# tiva_motor.net
KiCad netlist of a schematic drawn in EAGLE
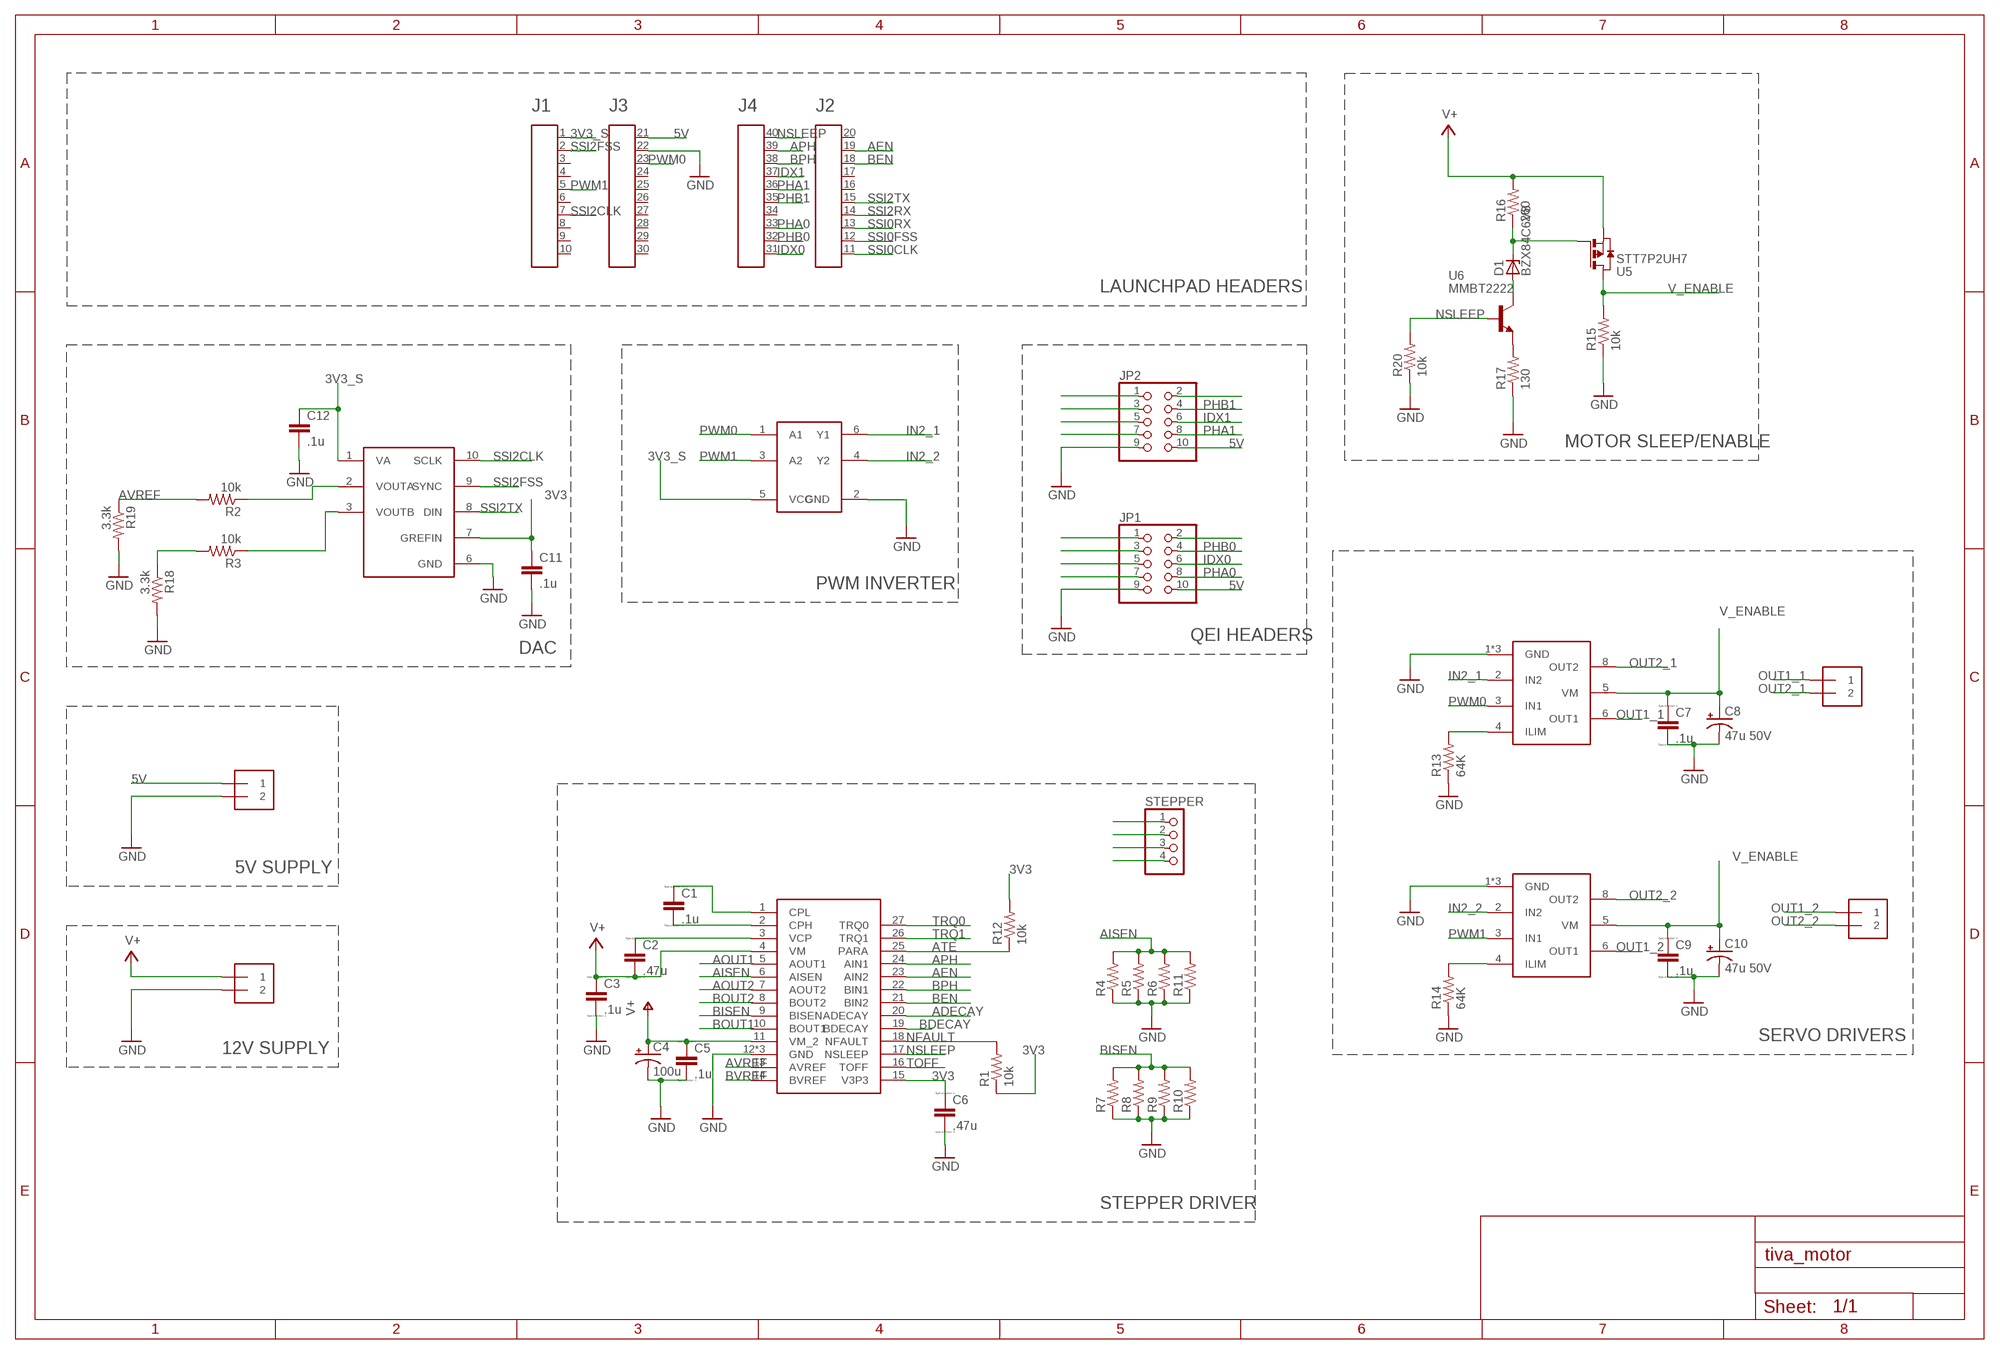
[diagram p0: schematic, sheet 1]

(export (version "E")
  (design (tool "Eeschema 10.0.6"))
  (components
    (comp (ref "5V")
      (value "1X2-3.5MM")
      (footprint "eagle-import:1X2-3.5MM")
      (libsource (lib "eagle-import") (part "1X2-3.5MM"))
    )
    (comp (ref "12V")
      (value "1X2-3.5MM")
      (footprint "eagle-import:1X2-3.5MM")
      (libsource (lib "eagle-import") (part "1X2-3.5MM"))
    )
    (comp (ref "A1")
      (value "HEADER4X10-BOOSTERPACK")
      (footprint "eagle-import:4X10-BOOSTERPACK")
      (libsource (lib "eagle-import") (part "HEADER4X10-BOOSTERPACK"))
    )
    (comp (ref "C1")
      (value ".1u")
      (footprint "eagle-import:C0603")
      (libsource (lib "eagle-import") (part "CC0603"))
    )
    (comp (ref "C2")
      (value ".47u")
      (footprint "eagle-import:C0603")
      (libsource (lib "eagle-import") (part "CC0603"))
    )
    (comp (ref "C3")
      (value ".1u")
      (footprint "eagle-import:C0603")
      (libsource (lib "eagle-import") (part "CC0603"))
    )
    (comp (ref "C4")
      (value "100u")
      (footprint "eagle-import:153CLV-0605")
      (libsource (lib "eagle-import") (part "CPOL-US153CLV-0605"))
    )
    (comp (ref "C5")
      (value ".1u")
      (footprint "eagle-import:C0603")
      (libsource (lib "eagle-import") (part "CC0603"))
    )
    (comp (ref "C6")
      (value ".47u")
      (footprint "eagle-import:C0603")
      (libsource (lib "eagle-import") (part "CC0603"))
    )
    (comp (ref "C7")
      (value ".1u")
      (footprint "eagle-import:C0603")
      (libsource (lib "eagle-import") (part "CC0603"))
    )
    (comp (ref "C8")
      (value "47u 50V")
      (footprint "eagle-import:153CLV-0605")
      (libsource (lib "eagle-import") (part "CPOL-US153CLV-0605"))
    )
    (comp (ref "C9")
      (value ".1u")
      (footprint "eagle-import:C0603")
      (libsource (lib "eagle-import") (part "CC0603"))
    )
    (comp (ref "C10")
      (value "47u 50V")
      (footprint "eagle-import:153CLV-0605")
      (libsource (lib "eagle-import") (part "CPOL-US153CLV-0605"))
    )
    (comp (ref "C11")
      (value ".1u")
      (footprint "eagle-import:C0402")
      (libsource (lib "eagle-import") (part "C-EUC0402"))
    )
    (comp (ref "C12")
      (value ".1u")
      (footprint "eagle-import:C0402")
      (libsource (lib "eagle-import") (part "C-EUC0402"))
    )
    (comp (ref "D1")
      (value "BZX84C6V8")
      (footprint "eagle-import:SOT-23")
      (libsource (lib "eagle-import") (part "BZX84C6V8"))
    )
    (comp (ref "JP1")
      (value "PINHD-2X5")
      (footprint "eagle-import:2X05")
      (libsource (lib "eagle-import") (part "PINHD-2X5"))
    )
    (comp (ref "JP2")
      (value "PINHD-2X5")
      (footprint "eagle-import:2X05")
      (libsource (lib "eagle-import") (part "PINHD-2X5"))
    )
    (comp (ref "M1")
      (value "1X2-3.5MM")
      (footprint "eagle-import:1X2-3.5MM")
      (libsource (lib "eagle-import") (part "1X2-3.5MM"))
    )
    (comp (ref "M2")
      (value "1X2-3.5MM")
      (footprint "eagle-import:1X2-3.5MM")
      (libsource (lib "eagle-import") (part "1X2-3.5MM"))
    )
    (comp (ref "R1")
      (value "10k")
      (footprint "eagle-import:R0402")
      (libsource (lib "eagle-import") (part "R-US_R0402"))
    )
    (comp (ref "R2")
      (value "10k")
      (footprint "eagle-import:R0603")
      (libsource (lib "eagle-import") (part "R-US_R0603"))
    )
    (comp (ref "R3")
      (value "10k")
      (footprint "eagle-import:R0603")
      (libsource (lib "eagle-import") (part "R-US_R0603"))
    )
    (comp (ref "R4")
      (value "R-US_R0603")
      (footprint "eagle-import:R0603")
      (libsource (lib "eagle-import") (part "R-US_R0603"))
    )
    (comp (ref "R5")
      (value "R-US_R0603")
      (footprint "eagle-import:R0603")
      (libsource (lib "eagle-import") (part "R-US_R0603"))
    )
    (comp (ref "R6")
      (value "R-US_R0603")
      (footprint "eagle-import:R0603")
      (libsource (lib "eagle-import") (part "R-US_R0603"))
    )
    (comp (ref "R7")
      (value "R-US_R0603")
      (footprint "eagle-import:R0603")
      (libsource (lib "eagle-import") (part "R-US_R0603"))
    )
    (comp (ref "R8")
      (value "R-US_R0603")
      (footprint "eagle-import:R0603")
      (libsource (lib "eagle-import") (part "R-US_R0603"))
    )
    (comp (ref "R9")
      (value "R-US_R0603")
      (footprint "eagle-import:R0603")
      (libsource (lib "eagle-import") (part "R-US_R0603"))
    )
    (comp (ref "R10")
      (value "R-US_R0603")
      (footprint "eagle-import:R0603")
      (libsource (lib "eagle-import") (part "R-US_R0603"))
    )
    (comp (ref "R11")
      (value "R-US_R0603")
      (footprint "eagle-import:R0603")
      (libsource (lib "eagle-import") (part "R-US_R0603"))
    )
    (comp (ref "R12")
      (value "10k")
      (footprint "eagle-import:R0402")
      (libsource (lib "eagle-import") (part "R-US_R0402"))
    )
    (comp (ref "R13")
      (value "64K")
      (footprint "eagle-import:R0603")
      (libsource (lib "eagle-import") (part "R-US_R0603"))
    )
    (comp (ref "R14")
      (value "64K")
      (footprint "eagle-import:R0603")
      (libsource (lib "eagle-import") (part "R-US_R0603"))
    )
    (comp (ref "R15")
      (value "10k")
      (footprint "eagle-import:R0402")
      (libsource (lib "eagle-import") (part "R-US_R0402"))
    )
    (comp (ref "R16")
      (value "260")
      (footprint "eagle-import:R0805")
      (libsource (lib "eagle-import") (part "R-US_R0805"))
    )
    (comp (ref "R17")
      (value "130")
      (footprint "eagle-import:R1206")
      (libsource (lib "eagle-import") (part "R-US_R1206"))
    )
    (comp (ref "R18")
      (value "3.3k")
      (footprint "eagle-import:R0603")
      (libsource (lib "eagle-import") (part "R-US_R0603"))
    )
    (comp (ref "R19")
      (value "3.3k")
      (footprint "eagle-import:R0603")
      (libsource (lib "eagle-import") (part "R-US_R0603"))
    )
    (comp (ref "R20")
      (value "10k")
      (footprint "eagle-import:R0402")
      (libsource (lib "eagle-import") (part "R-US_R0402"))
    )
    (comp (ref "STEPPER")
      (value "PINHD-1X4")
      (footprint "eagle-import:1X04")
      (libsource (lib "eagle-import") (part "PINHD-1X4"))
    )
    (comp (ref "U1")
      (value "DRV8881")
      (footprint "eagle-import:TSSOP28")
      (libsource (lib "eagle-import") (part "DRV8881"))
    )
    (comp (ref "U2")
      (value "DRV8871")
      (footprint "eagle-import:SOIC127P600X170-9N")
      (libsource (lib "eagle-import") (part "DRV8871"))
    )
    (comp (ref "U4")
      (value "DRV8871")
      (footprint "eagle-import:SOIC127P600X170-9N")
      (libsource (lib "eagle-import") (part "DRV8871"))
    )
    (comp (ref "U5")
      (value "STT7P2UH7")
      (footprint "eagle-import:SOT23-6")
      (libsource (lib "eagle-import") (part "STT7P2UH7"))
    )
    (comp (ref "U6")
      (value "MMBT2222")
      (footprint "eagle-import:SOT-23")
      (libsource (lib "eagle-import") (part "MMBT2222"))
    )
    (comp (ref "U8")
      (value "DAC082S085")
      (footprint "eagle-import:SOP50P490X110-10N")
      (libsource (lib "eagle-import") (part "DAC082S085"))
    )
    (comp (ref "U9")
      (value "NC7WZ14")
      (footprint "eagle-import:SC70-6")
      (libsource (lib "eagle-import") (part "NC7WZ14"))
    )
  )
  (nets
    (net (code "1") (name "/3V3") (class "Default")
      (node (ref "C11") (pin "1") (pinfunction "1_1") (pintype "passive"))
      (node (ref "C6") (pin "1") (pinfunction "1_1") (pintype "passive"))
      (node (ref "R1") (pin "1") (pinfunction "1_1") (pintype "passive"))
      (node (ref "R12") (pin "2") (pinfunction "2_2") (pintype "passive"))
      (node (ref "U1") (pin "15") (pinfunction "V3P3_15") (pintype "bidirectional"))
      (node (ref "U8") (pin "7") (pinfunction "GREFIN_7") (pintype "bidirectional"))
    )
    (net (code "2") (name "/3V3_S") (class "Default")
      (node (ref "A1") (pin "1") (pinfunction "P$1_1") (pintype "bidirectional"))
      (node (ref "C12") (pin "1") (pinfunction "1_1") (pintype "passive"))
      (node (ref "U8") (pin "1") (pinfunction "VA_1") (pintype "bidirectional"))
      (node (ref "U9") (pin "5") (pinfunction "VCC_5") (pintype "bidirectional"))
    )
    (net (code "3") (name "/5V") (class "Default")
      (node (ref "5V") (pin "1") (pinfunction "1_1") (pintype "passive"))
      (node (ref "A1") (pin "21") (pinfunction "P$21_21") (pintype "bidirectional"))
      (node (ref "JP1") (pin "10") (pinfunction "10_10") (pintype "passive"))
      (node (ref "JP2") (pin "10") (pinfunction "10_10") (pintype "passive"))
    )
    (net (code "4") (name "/ADECAY") (class "Default")
      (node (ref "U1") (pin "20") (pinfunction "ADECAY_20") (pintype "bidirectional"))
    )
    (net (code "5") (name "/AEN") (class "Default")
      (node (ref "A1") (pin "19") (pinfunction "P$19_19") (pintype "bidirectional"))
      (node (ref "U1") (pin "23") (pinfunction "AIN2_23") (pintype "bidirectional"))
    )
    (net (code "6") (name "/AISEN") (class "Default")
      (node (ref "R11") (pin "2") (pinfunction "2_2") (pintype "passive"))
      (node (ref "R4") (pin "2") (pinfunction "2_2") (pintype "passive"))
      (node (ref "R5") (pin "2") (pinfunction "2_2") (pintype "passive"))
      (node (ref "R6") (pin "2") (pinfunction "2_2") (pintype "passive"))
      (node (ref "U1") (pin "6") (pinfunction "AISEN_6") (pintype "bidirectional"))
    )
    (net (code "7") (name "/AOUT1") (class "Default")
      (node (ref "STEPPER") (pin "1") (pinfunction "1_1") (pintype "passive"))
      (node (ref "U1") (pin "5") (pinfunction "AOUT1_5") (pintype "bidirectional"))
    )
    (net (code "8") (name "/AOUT2") (class "Default")
      (node (ref "STEPPER") (pin "2") (pinfunction "2_2") (pintype "passive"))
      (node (ref "U1") (pin "7") (pinfunction "AOUT2_7") (pintype "bidirectional"))
    )
    (net (code "9") (name "/APH") (class "Default")
      (node (ref "A1") (pin "39") (pinfunction "P$39_39") (pintype "bidirectional"))
      (node (ref "U1") (pin "24") (pinfunction "AIN1_24") (pintype "bidirectional"))
    )
    (net (code "10") (name "/ATE") (class "Default")
      (node (ref "R12") (pin "1") (pinfunction "1_1") (pintype "passive"))
      (node (ref "U1") (pin "25") (pinfunction "PARA_25") (pintype "bidirectional"))
    )
    (net (code "11") (name "/AVREF") (class "Default")
      (node (ref "R19") (pin "1") (pinfunction "1_1") (pintype "passive"))
      (node (ref "R2") (pin "2") (pinfunction "2_2") (pintype "passive"))
      (node (ref "U1") (pin "13") (pinfunction "AVREF_13") (pintype "bidirectional"))
    )
    (net (code "12") (name "/BDECAY") (class "Default")
      (node (ref "U1") (pin "19") (pinfunction "BDECAY_19") (pintype "bidirectional"))
    )
    (net (code "13") (name "/BEN") (class "Default")
      (node (ref "A1") (pin "18") (pinfunction "P$18_18") (pintype "bidirectional"))
      (node (ref "U1") (pin "21") (pinfunction "BIN2_21") (pintype "bidirectional"))
    )
    (net (code "14") (name "/BISEN") (class "Default")
      (node (ref "R10") (pin "2") (pinfunction "2_2") (pintype "passive"))
      (node (ref "R7") (pin "2") (pinfunction "2_2") (pintype "passive"))
      (node (ref "R8") (pin "2") (pinfunction "2_2") (pintype "passive"))
      (node (ref "R9") (pin "2") (pinfunction "2_2") (pintype "passive"))
      (node (ref "U1") (pin "9") (pinfunction "BISEN_9") (pintype "bidirectional"))
    )
    (net (code "15") (name "/BOUT1") (class "Default")
      (node (ref "STEPPER") (pin "3") (pinfunction "3_3") (pintype "passive"))
      (node (ref "U1") (pin "10") (pinfunction "BOUT1_10") (pintype "bidirectional"))
    )
    (net (code "16") (name "/BOUT2") (class "Default")
      (node (ref "STEPPER") (pin "4") (pinfunction "4_4") (pintype "passive"))
      (node (ref "U1") (pin "8") (pinfunction "BOUT2_8") (pintype "bidirectional"))
    )
    (net (code "17") (name "/BPH") (class "Default")
      (node (ref "A1") (pin "38") (pinfunction "P$38_38") (pintype "bidirectional"))
      (node (ref "U1") (pin "22") (pinfunction "BIN1_22") (pintype "bidirectional"))
    )
    (net (code "18") (name "/BVREF") (class "Default")
      (node (ref "R18") (pin "1") (pinfunction "1_1") (pintype "passive"))
      (node (ref "R3") (pin "2") (pinfunction "2_2") (pintype "passive"))
      (node (ref "U1") (pin "14") (pinfunction "BVREF_14") (pintype "bidirectional"))
    )
    (net (code "19") (name "/IDX0") (class "Default")
      (node (ref "A1") (pin "31") (pinfunction "P$31_31") (pintype "bidirectional"))
      (node (ref "JP1") (pin "6") (pinfunction "6_6") (pintype "passive"))
    )
    (net (code "20") (name "/IDX1") (class "Default")
      (node (ref "A1") (pin "37") (pinfunction "P$37_37") (pintype "bidirectional"))
      (node (ref "JP2") (pin "6") (pinfunction "6_6") (pintype "passive"))
    )
    (net (code "21") (name "/IN2_1") (class "Default")
      (node (ref "U2") (pin "2") (pinfunction "IN2_2") (pintype "bidirectional"))
      (node (ref "U9") (pin "6") (pinfunction "Y1_6") (pintype "bidirectional"))
    )
    (net (code "22") (name "/IN2_2") (class "Default")
      (node (ref "U4") (pin "2") (pinfunction "IN2_2") (pintype "bidirectional"))
      (node (ref "U9") (pin "4") (pinfunction "Y2_4") (pintype "bidirectional"))
    )
    (net (code "23") (name "/NFAULT") (class "Default")
      (node (ref "R1") (pin "2") (pinfunction "2_2") (pintype "passive"))
      (node (ref "U1") (pin "18") (pinfunction "NFAULT_18") (pintype "bidirectional"))
    )
    (net (code "24") (name "/NSLEEP") (class "Default")
      (node (ref "A1") (pin "40") (pinfunction "P$40_40") (pintype "bidirectional"))
      (node (ref "R20") (pin "2") (pinfunction "2_2") (pintype "passive"))
      (node (ref "U1") (pin "17") (pinfunction "NSLEEP_17") (pintype "bidirectional"))
      (node (ref "U6") (pin "1") (pinfunction "B_1") (pintype "passive"))
    )
    (net (code "25") (name "/OUT1_1") (class "Default")
      (node (ref "M1") (pin "1") (pinfunction "1_1") (pintype "passive"))
      (node (ref "U2") (pin "6") (pinfunction "OUT1_6") (pintype "bidirectional"))
    )
    (net (code "26") (name "/OUT1_2") (class "Default")
      (node (ref "M2") (pin "1") (pinfunction "1_1") (pintype "passive"))
      (node (ref "U4") (pin "6") (pinfunction "OUT1_6") (pintype "bidirectional"))
    )
    (net (code "27") (name "/OUT2_1") (class "Default")
      (node (ref "M1") (pin "2") (pinfunction "2_2") (pintype "passive"))
      (node (ref "U2") (pin "8") (pinfunction "OUT2_8") (pintype "bidirectional"))
    )
    (net (code "28") (name "/OUT2_2") (class "Default")
      (node (ref "M2") (pin "2") (pinfunction "2_2") (pintype "passive"))
      (node (ref "U4") (pin "8") (pinfunction "OUT2_8") (pintype "bidirectional"))
    )
    (net (code "29") (name "/PHA0") (class "Default")
      (node (ref "A1") (pin "33") (pinfunction "P$33_33") (pintype "bidirectional"))
      (node (ref "JP1") (pin "8") (pinfunction "8_8") (pintype "passive"))
    )
    (net (code "30") (name "/PHA1") (class "Default")
      (node (ref "A1") (pin "36") (pinfunction "P$36_36") (pintype "bidirectional"))
      (node (ref "JP2") (pin "8") (pinfunction "8_8") (pintype "passive"))
    )
    (net (code "31") (name "/PHB0") (class "Default")
      (node (ref "A1") (pin "32") (pinfunction "P$32_32") (pintype "bidirectional"))
      (node (ref "JP1") (pin "4") (pinfunction "4_4") (pintype "passive"))
    )
    (net (code "32") (name "/PHB1") (class "Default")
      (node (ref "A1") (pin "35") (pinfunction "P$35_35") (pintype "bidirectional"))
      (node (ref "JP2") (pin "4") (pinfunction "4_4") (pintype "passive"))
    )
    (net (code "33") (name "/PWM0") (class "Default")
      (node (ref "A1") (pin "23") (pinfunction "P$23_23") (pintype "bidirectional"))
      (node (ref "U2") (pin "3") (pinfunction "IN1_3") (pintype "bidirectional"))
      (node (ref "U9") (pin "1") (pinfunction "A1_1") (pintype "bidirectional"))
    )
    (net (code "34") (name "/PWM1") (class "Default")
      (node (ref "A1") (pin "5") (pinfunction "P$5_5") (pintype "bidirectional"))
      (node (ref "U4") (pin "3") (pinfunction "IN1_3") (pintype "bidirectional"))
      (node (ref "U9") (pin "3") (pinfunction "A2_3") (pintype "bidirectional"))
    )
    (net (code "35") (name "/SSI0CLK") (class "Default")
      (node (ref "A1") (pin "11") (pinfunction "P$11_11") (pintype "bidirectional"))
    )
    (net (code "36") (name "/SSI0FSS") (class "Default")
      (node (ref "A1") (pin "12") (pinfunction "P$12_12") (pintype "bidirectional"))
    )
    (net (code "37") (name "/SSI0RX") (class "Default")
      (node (ref "A1") (pin "13") (pinfunction "P$13_13") (pintype "bidirectional"))
    )
    (net (code "38") (name "/SSI2CLK") (class "Default")
      (node (ref "A1") (pin "7") (pinfunction "P$7_7") (pintype "bidirectional"))
      (node (ref "U8") (pin "10") (pinfunction "SCLK_10") (pintype "bidirectional"))
    )
    (net (code "39") (name "/SSI2FSS") (class "Default")
      (node (ref "A1") (pin "2") (pinfunction "P$2_2") (pintype "bidirectional"))
      (node (ref "U8") (pin "9") (pinfunction "SYNC_9") (pintype "bidirectional"))
    )
    (net (code "40") (name "/SSI2RX") (class "Default")
      (node (ref "A1") (pin "14") (pinfunction "P$14_14") (pintype "bidirectional"))
    )
    (net (code "41") (name "/SSI2TX") (class "Default")
      (node (ref "A1") (pin "15") (pinfunction "P$15_15") (pintype "bidirectional"))
      (node (ref "U8") (pin "8") (pinfunction "DIN_8") (pintype "bidirectional"))
    )
    (net (code "42") (name "/TOFF") (class "Default")
      (node (ref "U1") (pin "16") (pinfunction "TOFF_16") (pintype "bidirectional"))
    )
    (net (code "43") (name "/TRQ0") (class "Default")
      (node (ref "U1") (pin "27") (pinfunction "TRQ0_27") (pintype "bidirectional"))
    )
    (net (code "44") (name "/TRQ1") (class "Default")
      (node (ref "U1") (pin "26") (pinfunction "TRQ1_26") (pintype "bidirectional"))
    )
    (net (code "45") (name "/V_ENABLE") (class "Default")
      (node (ref "C10") (pin "+") (pinfunction "+_+") (pintype "passive"))
      (node (ref "C7") (pin "1") (pinfunction "1_1") (pintype "passive"))
      (node (ref "C8") (pin "+") (pinfunction "+_+") (pintype "passive"))
      (node (ref "C9") (pin "1") (pinfunction "1_1") (pintype "passive"))
      (node (ref "R15") (pin "2") (pinfunction "2_2") (pintype "passive"))
      (node (ref "U2") (pin "5") (pinfunction "VM_5") (pintype "bidirectional"))
      (node (ref "U4") (pin "5") (pinfunction "VM_5") (pintype "bidirectional"))
      (node (ref "U5") (pin "1") (pinfunction "D_1") (pintype "passive"))
      (node (ref "U5") (pin "2") (pinfunction "D_2") (pintype "passive"))
      (node (ref "U5") (pin "5") (pinfunction "D_5") (pintype "passive"))
      (node (ref "U5") (pin "6") (pinfunction "D_6") (pintype "passive"))
    )
    (net (code "46") (name "GND") (class "Default")
      (node (ref "12V") (pin "2") (pinfunction "2_2") (pintype "passive"))
      (node (ref "5V") (pin "2") (pinfunction "2_2") (pintype "passive"))
      (node (ref "A1") (pin "22") (pinfunction "P$22_22") (pintype "bidirectional"))
      (node (ref "C10") (pin "-") (pinfunction "-_-") (pintype "passive"))
      (node (ref "C11") (pin "2") (pinfunction "2_2") (pintype "passive"))
      (node (ref "C12") (pin "2") (pinfunction "2_2") (pintype "passive"))
      (node (ref "C3") (pin "2") (pinfunction "2_2") (pintype "passive"))
      (node (ref "C4") (pin "-") (pinfunction "-_-") (pintype "passive"))
      (node (ref "C5") (pin "2") (pinfunction "2_2") (pintype "passive"))
      (node (ref "C6") (pin "2") (pinfunction "2_2") (pintype "passive"))
      (node (ref "C7") (pin "2") (pinfunction "2_2") (pintype "passive"))
      (node (ref "C8") (pin "-") (pinfunction "-_-") (pintype "passive"))
      (node (ref "C9") (pin "2") (pinfunction "2_2") (pintype "passive"))
      (node (ref "JP1") (pin "9") (pinfunction "9_9") (pintype "passive"))
      (node (ref "JP2") (pin "9") (pinfunction "9_9") (pintype "passive"))
      (node (ref "R10") (pin "1") (pinfunction "1_1") (pintype "passive"))
      (node (ref "R11") (pin "1") (pinfunction "1_1") (pintype "passive"))
      (node (ref "R13") (pin "1") (pinfunction "1_1") (pintype "passive"))
      (node (ref "R14") (pin "1") (pinfunction "1_1") (pintype "passive"))
      (node (ref "R15") (pin "1") (pinfunction "1_1") (pintype "passive"))
      (node (ref "R17") (pin "1") (pinfunction "1_1") (pintype "passive"))
      (node (ref "R18") (pin "2") (pinfunction "2_2") (pintype "passive"))
      (node (ref "R19") (pin "2") (pinfunction "2_2") (pintype "passive"))
      (node (ref "R20") (pin "1") (pinfunction "1_1") (pintype "passive"))
      (node (ref "R4") (pin "1") (pinfunction "1_1") (pintype "passive"))
      (node (ref "R5") (pin "1") (pinfunction "1_1") (pintype "passive"))
      (node (ref "R6") (pin "1") (pinfunction "1_1") (pintype "passive"))
      (node (ref "R7") (pin "1") (pinfunction "1_1") (pintype "passive"))
      (node (ref "R8") (pin "1") (pinfunction "1_1") (pintype "passive"))
      (node (ref "R9") (pin "1") (pinfunction "1_1") (pintype "passive"))
      (node (ref "U1") (pin "12") (pinfunction "GND_12") (pintype "bidirectional"))
      (node (ref "U1") (pin "28") (pinfunction "GND_28") (pintype "bidirectional"))
      (node (ref "U1") (pin "P$1") (pinfunction "GND_P$1") (pintype "bidirectional"))
      (node (ref "U2") (pin "1") (pinfunction "GND_1") (pintype "bidirectional"))
      (node (ref "U2") (pin "7") (pinfunction "GND_7") (pintype "bidirectional"))
      (node (ref "U2") (pin "9") (pinfunction "GND_9") (pintype "bidirectional"))
      (node (ref "U4") (pin "1") (pinfunction "GND_1") (pintype "bidirectional"))
      (node (ref "U4") (pin "7") (pinfunction "GND_7") (pintype "bidirectional"))
      (node (ref "U4") (pin "9") (pinfunction "GND_9") (pintype "bidirectional"))
      (node (ref "U8") (pin "6") (pinfunction "GND_6") (pintype "bidirectional"))
      (node (ref "U9") (pin "2") (pinfunction "GND_2") (pintype "bidirectional"))
    )
    (net (code "47") (name "Net-(D1-A)") (class "Default")
      (node (ref "D1") (pin "1") (pinfunction "A_1") (pintype "passive"))
      (node (ref "U6") (pin "3") (pinfunction "C_3") (pintype "passive"))
    )
    (net (code "48") (name "Net-(D1-C)") (class "Default")
      (node (ref "D1") (pin "3") (pinfunction "C_3") (pintype "passive"))
      (node (ref "R16") (pin "1") (pinfunction "1_1") (pintype "passive"))
      (node (ref "U5") (pin "3") (pinfunction "G_3") (pintype "passive"))
    )
    (net (code "49") (name "Net-(U1-CPH)") (class "Default")
      (node (ref "C1") (pin "2") (pinfunction "2_2") (pintype "passive"))
      (node (ref "U1") (pin "2") (pinfunction "CPH_2") (pintype "bidirectional"))
    )
    (net (code "50") (name "Net-(U1-CPL)") (class "Default")
      (node (ref "C1") (pin "1") (pinfunction "1_1") (pintype "passive"))
      (node (ref "U1") (pin "1") (pinfunction "CPL_1") (pintype "bidirectional"))
    )
    (net (code "51") (name "Net-(U1-VCP)") (class "Default")
      (node (ref "C2") (pin "1") (pinfunction "1_1") (pintype "passive"))
      (node (ref "U1") (pin "3") (pinfunction "VCP_3") (pintype "bidirectional"))
    )
    (net (code "52") (name "Net-(U2-ILIM)") (class "Default")
      (node (ref "R13") (pin "2") (pinfunction "2_2") (pintype "passive"))
      (node (ref "U2") (pin "4") (pinfunction "ILIM_4") (pintype "bidirectional"))
    )
    (net (code "53") (name "Net-(U4-ILIM)") (class "Default")
      (node (ref "R14") (pin "2") (pinfunction "2_2") (pintype "passive"))
      (node (ref "U4") (pin "4") (pinfunction "ILIM_4") (pintype "bidirectional"))
    )
    (net (code "54") (name "Net-(U6-E)") (class "Default")
      (node (ref "R17") (pin "2") (pinfunction "2_2") (pintype "passive"))
      (node (ref "U6") (pin "2") (pinfunction "E_2") (pintype "passive"))
    )
    (net (code "55") (name "Net-(U8-VOUTA)") (class "Default")
      (node (ref "R2") (pin "1") (pinfunction "1_1") (pintype "passive"))
      (node (ref "U8") (pin "2") (pinfunction "VOUTA_2") (pintype "bidirectional"))
    )
    (net (code "56") (name "Net-(U8-VOUTB)") (class "Default")
      (node (ref "R3") (pin "1") (pinfunction "1_1") (pintype "passive"))
      (node (ref "U8") (pin "3") (pinfunction "VOUTB_3") (pintype "bidirectional"))
    )
    (net (code "57") (name "V+") (class "Default")
      (node (ref "12V") (pin "1") (pinfunction "1_1") (pintype "passive"))
      (node (ref "C2") (pin "2") (pinfunction "2_2") (pintype "passive"))
      (node (ref "C3") (pin "1") (pinfunction "1_1") (pintype "passive"))
      (node (ref "C4") (pin "+") (pinfunction "+_+") (pintype "passive"))
      (node (ref "C5") (pin "1") (pinfunction "1_1") (pintype "passive"))
      (node (ref "R16") (pin "2") (pinfunction "2_2") (pintype "passive"))
      (node (ref "U1") (pin "11") (pinfunction "VM_2_11") (pintype "bidirectional"))
      (node (ref "U1") (pin "4") (pinfunction "VM_4") (pintype "bidirectional"))
      (node (ref "U5") (pin "4") (pinfunction "S_4") (pintype "passive"))
    )
    (net (code "58") (name "unconnected-(A1-P$3-Pad3)") (class "Default")
      (node (ref "A1") (pin "3") (pinfunction "P$3_3") (pintype "bidirectional"))
    )
    (net (code "59") (name "unconnected-(A1-P$4-Pad4)") (class "Default")
      (node (ref "A1") (pin "4") (pinfunction "P$4_4") (pintype "bidirectional"))
    )
    (net (code "60") (name "unconnected-(A1-P$6-Pad6)") (class "Default")
      (node (ref "A1") (pin "6") (pinfunction "P$6_6") (pintype "bidirectional"))
    )
    (net (code "61") (name "unconnected-(A1-P$8-Pad8)") (class "Default")
      (node (ref "A1") (pin "8") (pinfunction "P$8_8") (pintype "bidirectional"))
    )
    (net (code "62") (name "unconnected-(A1-P$9-Pad9)") (class "Default")
      (node (ref "A1") (pin "9") (pinfunction "P$9_9") (pintype "bidirectional"))
    )
    (net (code "63") (name "unconnected-(A1-P$10-Pad10)") (class "Default")
      (node (ref "A1") (pin "10") (pinfunction "P$10_10") (pintype "bidirectional"))
    )
    (net (code "64") (name "unconnected-(A1-P$16-Pad16)") (class "Default")
      (node (ref "A1") (pin "16") (pinfunction "P$16_16") (pintype "bidirectional"))
    )
    (net (code "65") (name "unconnected-(A1-P$17-Pad17)") (class "Default")
      (node (ref "A1") (pin "17") (pinfunction "P$17_17") (pintype "bidirectional"))
    )
    (net (code "66") (name "unconnected-(A1-P$20-Pad20)") (class "Default")
      (node (ref "A1") (pin "20") (pinfunction "P$20_20") (pintype "bidirectional"))
    )
    (net (code "67") (name "unconnected-(A1-P$24-Pad24)") (class "Default")
      (node (ref "A1") (pin "24") (pinfunction "P$24_24") (pintype "bidirectional"))
    )
    (net (code "68") (name "unconnected-(A1-P$25-Pad25)") (class "Default")
      (node (ref "A1") (pin "25") (pinfunction "P$25_25") (pintype "bidirectional"))
    )
    (net (code "69") (name "unconnected-(A1-P$26-Pad26)") (class "Default")
      (node (ref "A1") (pin "26") (pinfunction "P$26_26") (pintype "bidirectional"))
    )
    (net (code "70") (name "unconnected-(A1-P$27-Pad27)") (class "Default")
      (node (ref "A1") (pin "27") (pinfunction "P$27_27") (pintype "bidirectional"))
    )
    (net (code "71") (name "unconnected-(A1-P$28-Pad28)") (class "Default")
      (node (ref "A1") (pin "28") (pinfunction "P$28_28") (pintype "bidirectional"))
    )
    (net (code "72") (name "unconnected-(A1-P$29-Pad29)") (class "Default")
      (node (ref "A1") (pin "29") (pinfunction "P$29_29") (pintype "bidirectional"))
    )
    (net (code "73") (name "unconnected-(A1-P$30-Pad30)") (class "Default")
      (node (ref "A1") (pin "30") (pinfunction "P$30_30") (pintype "bidirectional"))
    )
    (net (code "74") (name "unconnected-(A1-P$34-Pad34)") (class "Default")
      (node (ref "A1") (pin "34") (pinfunction "P$34_34") (pintype "bidirectional"))
    )
    (net (code "75") (name "unconnected-(JP1-Pad1)") (class "Default")
      (node (ref "JP1") (pin "1") (pinfunction "1_1") (pintype "passive"))
    )
    (net (code "76") (name "unconnected-(JP1-Pad2)") (class "Default")
      (node (ref "JP1") (pin "2") (pinfunction "2_2") (pintype "passive"))
    )
    (net (code "77") (name "unconnected-(JP1-Pad3)") (class "Default")
      (node (ref "JP1") (pin "3") (pinfunction "3_3") (pintype "passive"))
    )
    (net (code "78") (name "unconnected-(JP1-Pad5)") (class "Default")
      (node (ref "JP1") (pin "5") (pinfunction "5_5") (pintype "passive"))
    )
    (net (code "79") (name "unconnected-(JP1-Pad7)") (class "Default")
      (node (ref "JP1") (pin "7") (pinfunction "7_7") (pintype "passive"))
    )
    (net (code "80") (name "unconnected-(JP2-Pad1)") (class "Default")
      (node (ref "JP2") (pin "1") (pinfunction "1_1") (pintype "passive"))
    )
    (net (code "81") (name "unconnected-(JP2-Pad2)") (class "Default")
      (node (ref "JP2") (pin "2") (pinfunction "2_2") (pintype "passive"))
    )
    (net (code "82") (name "unconnected-(JP2-Pad3)") (class "Default")
      (node (ref "JP2") (pin "3") (pinfunction "3_3") (pintype "passive"))
    )
    (net (code "83") (name "unconnected-(JP2-Pad5)") (class "Default")
      (node (ref "JP2") (pin "5") (pinfunction "5_5") (pintype "passive"))
    )
    (net (code "84") (name "unconnected-(JP2-Pad7)") (class "Default")
      (node (ref "JP2") (pin "7") (pinfunction "7_7") (pintype "passive"))
    )
  )
)
